# PCB-AC2.net
KiCad netlist of a schematic drawn in EAGLE
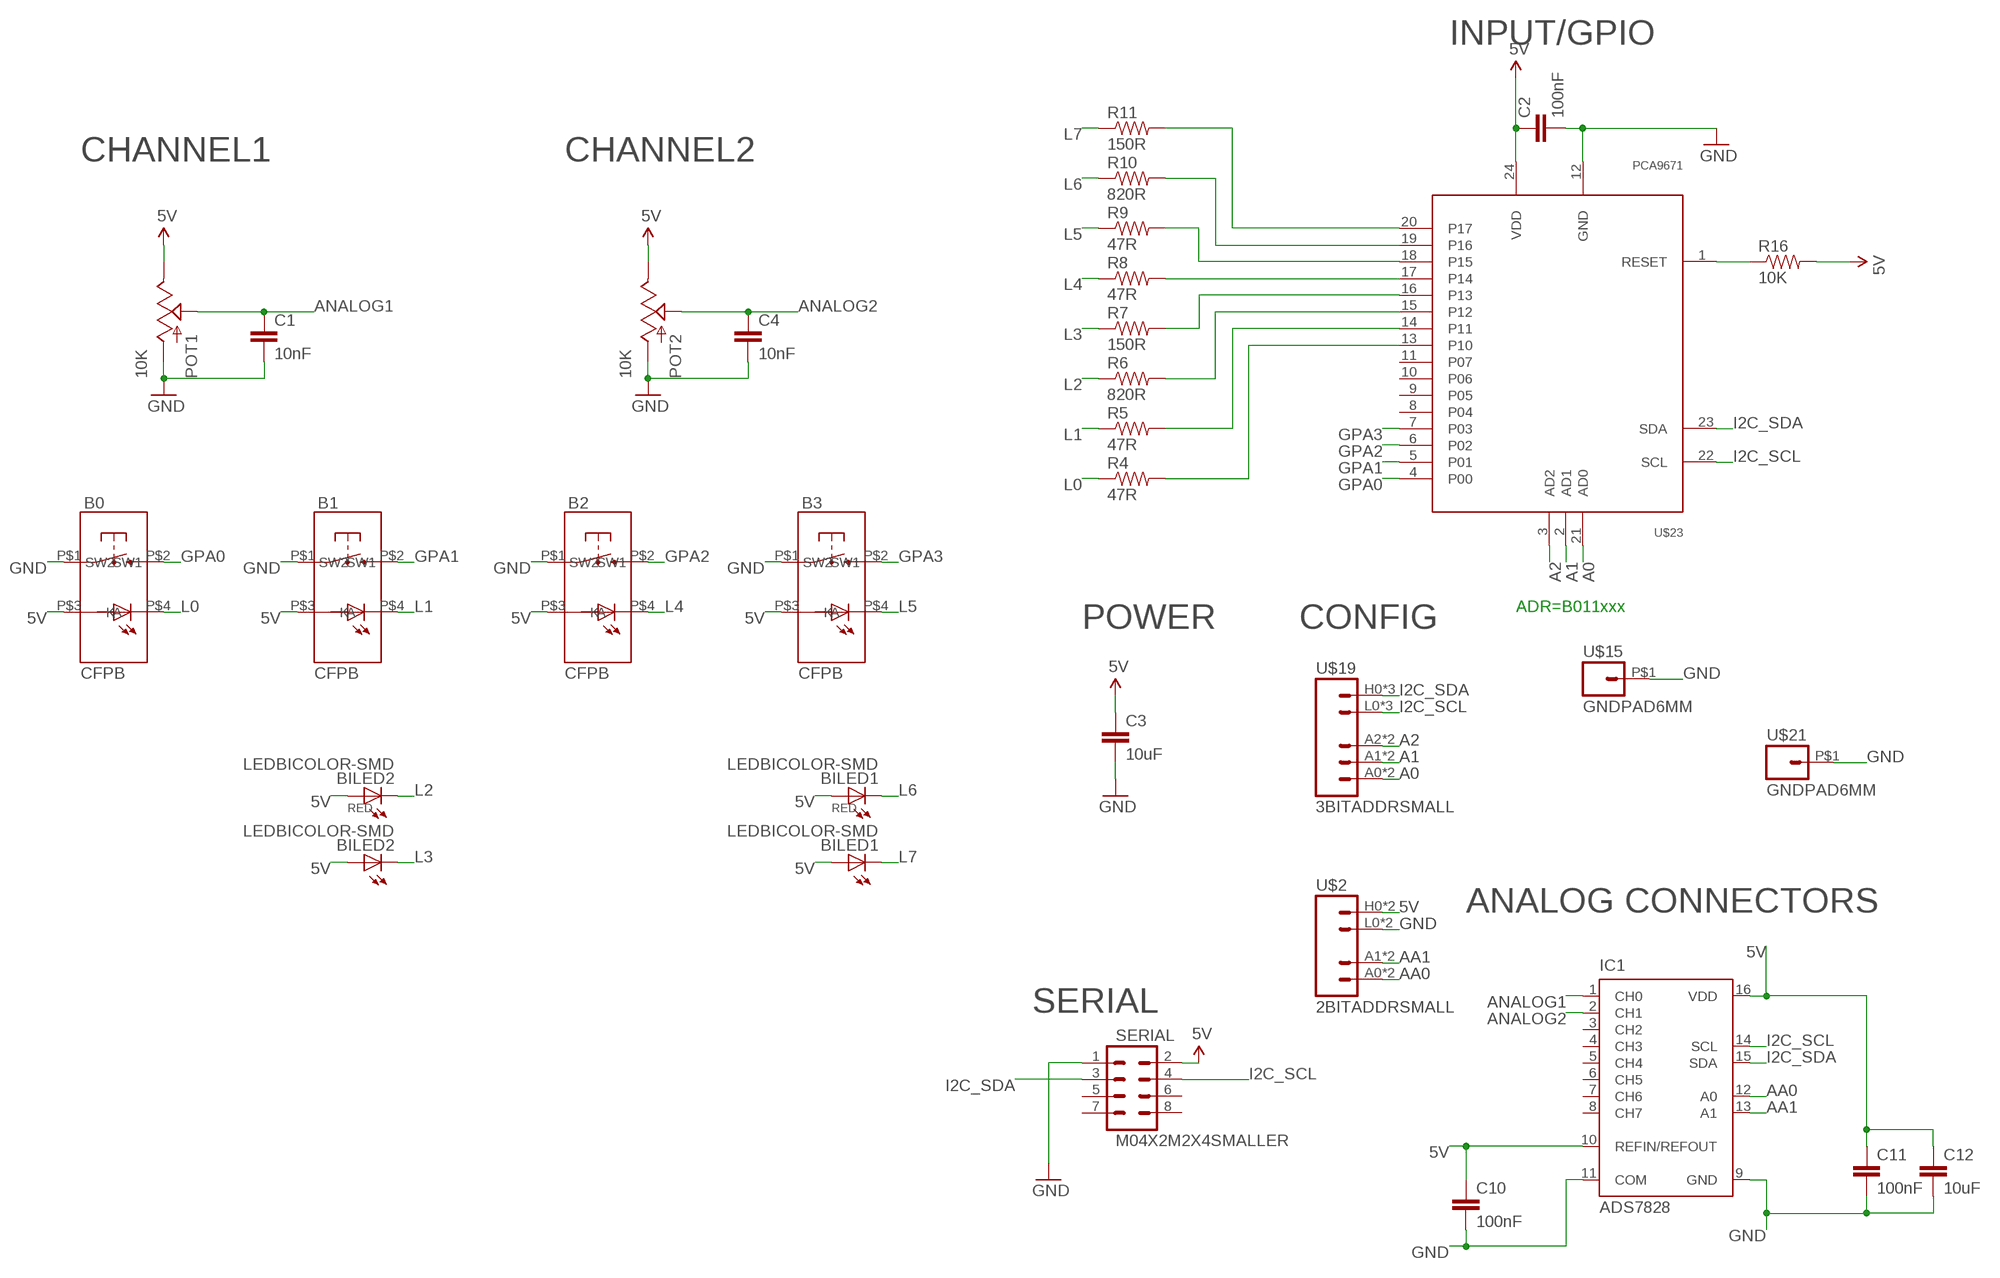
[diagram p0: schematic, sheet 1]

(export (version "E")
  (design (tool "Eeschema 10.0.6"))
  (components
    (comp (ref "B0")
      (value "CFPB")
      (footprint "eagle-import:CFPB-6_9MM")
      (libsource (lib "eagle-import") (part "CFPB"))
    )
    (comp (ref "B1")
      (value "CFPB")
      (footprint "eagle-import:CFPB-6_9MM")
      (libsource (lib "eagle-import") (part "CFPB"))
    )
    (comp (ref "B2")
      (value "CFPB")
      (footprint "eagle-import:CFPB-6_9MM")
      (libsource (lib "eagle-import") (part "CFPB"))
    )
    (comp (ref "B3")
      (value "CFPB")
      (footprint "eagle-import:CFPB-6_9MM")
      (libsource (lib "eagle-import") (part "CFPB"))
    )
    (comp (ref "BILED1")
      (value "LEDBICOLOR-SMD")
      (footprint "eagle-import:LEDBICOLOR-SMD")
      (libsource (lib "eagle-import") (part "LEDBICOLOR-SMD"))
    )
    (comp (ref "BILED2")
      (value "LEDBICOLOR-SMD")
      (footprint "eagle-import:LEDBICOLOR-SMD")
      (libsource (lib "eagle-import") (part "LEDBICOLOR-SMD"))
    )
    (comp (ref "C1")
      (value "10nF")
      (footprint "eagle-import:0603-CAP")
      (libsource (lib "eagle-import") (part "CAP0603-CAP"))
    )
    (comp (ref "C2")
      (value "100nF")
      (footprint "eagle-import:0603-CAP")
      (libsource (lib "eagle-import") (part "CAP0603-CAP"))
    )
    (comp (ref "C3")
      (value "10uF")
      (footprint "eagle-import:0805")
      (libsource (lib "eagle-import") (part "CAP0805"))
    )
    (comp (ref "C4")
      (value "10nF")
      (footprint "eagle-import:0603-CAP")
      (libsource (lib "eagle-import") (part "CAP0603-CAP"))
    )
    (comp (ref "C10")
      (value "100nF")
      (footprint "eagle-import:0603-CAP")
      (libsource (lib "eagle-import") (part "CAP0603-CAP"))
    )
    (comp (ref "C11")
      (value "100nF")
      (footprint "eagle-import:0603-CAP")
      (libsource (lib "eagle-import") (part "CAP0603-CAP"))
    )
    (comp (ref "C12")
      (value "10uF")
      (footprint "eagle-import:0805")
      (libsource (lib "eagle-import") (part "CAP0805"))
    )
    (comp (ref "IC1")
      (value "ADS7828")
      (footprint "eagle-import:TSSOP16-PW")
      (fields (field (name "MF") "TEXAS INSTRUMENTS") (field (name "MPN") "ADS7828E/250"))
      (libsource (lib "eagle-import") (part "ADS7828"))
    )
    (comp (ref "POT1")
      (value "10K")
      (footprint "eagle-import:ALPS_POT")
      (libsource (lib "eagle-import") (part "POT"))
    )
    (comp (ref "POT2")
      (value "10K")
      (footprint "eagle-import:ALPS_POT")
      (libsource (lib "eagle-import") (part "POT"))
    )
    (comp (ref "R4")
      (value "47R")
      (footprint "eagle-import:0603-RES")
      (libsource (lib "eagle-import") (part "RESISTOR0603-RES"))
    )
    (comp (ref "R5")
      (value "47R")
      (footprint "eagle-import:0603-RES")
      (libsource (lib "eagle-import") (part "RESISTOR0603-RES"))
    )
    (comp (ref "R6")
      (value "820R")
      (footprint "eagle-import:0603-RES")
      (libsource (lib "eagle-import") (part "RESISTOR0603-RES"))
    )
    (comp (ref "R7")
      (value "150R")
      (footprint "eagle-import:0603-RES")
      (libsource (lib "eagle-import") (part "RESISTOR0603-RES"))
    )
    (comp (ref "R8")
      (value "47R")
      (footprint "eagle-import:0603-RES")
      (libsource (lib "eagle-import") (part "RESISTOR0603-RES"))
    )
    (comp (ref "R9")
      (value "47R")
      (footprint "eagle-import:0603-RES")
      (libsource (lib "eagle-import") (part "RESISTOR0603-RES"))
    )
    (comp (ref "R10")
      (value "820R")
      (footprint "eagle-import:0603-RES")
      (libsource (lib "eagle-import") (part "RESISTOR0603-RES"))
    )
    (comp (ref "R11")
      (value "150R")
      (footprint "eagle-import:0603-RES")
      (libsource (lib "eagle-import") (part "RESISTOR0603-RES"))
    )
    (comp (ref "R16")
      (value "10K")
      (footprint "eagle-import:0603-RES")
      (libsource (lib "eagle-import") (part "RESISTOR0603-RES"))
    )
    (comp (ref "SERIAL")
      (value "M04X2M2X4SMALLER")
      (footprint "eagle-import:M2X4SMALLER")
      (libsource (lib "eagle-import") (part "M04X2M2X4SMALLER"))
    )
    (comp (ref "U$2")
      (value "2BITADDRSMALL")
      (footprint "eagle-import:2BITADDR_SMALL")
      (libsource (lib "eagle-import") (part "2BITADDRSMALL"))
    )
    (comp (ref "U$15")
      (value "GNDPAD6MM")
      (footprint "eagle-import:3.2MMPAD6MM")
      (libsource (lib "eagle-import") (part "GNDPAD6MM"))
    )
    (comp (ref "U$19")
      (value "3BITADDRSMALL")
      (footprint "eagle-import:3BITADDR_SMALL")
      (libsource (lib "eagle-import") (part "3BITADDRSMALL"))
    )
    (comp (ref "U$21")
      (value "GNDPAD6MM")
      (footprint "eagle-import:3.2MMPAD6MM")
      (libsource (lib "eagle-import") (part "GNDPAD6MM"))
    )
    (comp (ref "U$23")
      (value "PCA9671")
      (footprint "eagle-import:TSSOP24")
      (libsource (lib "eagle-import") (part "PCA9671"))
    )
  )
  (nets
    (net (code "1") (name "5V") (class "Default")
      (node (ref "B0") (pin "P$3") (pinfunction "A_P$3") (pintype "bidirectional"))
      (node (ref "B1") (pin "P$3") (pinfunction "A_P$3") (pintype "bidirectional"))
      (node (ref "B2") (pin "P$3") (pinfunction "A_P$3") (pintype "bidirectional"))
      (node (ref "B3") (pin "P$3") (pinfunction "A_P$3") (pintype "bidirectional"))
      (node (ref "BILED1") (pin "P$1") (pinfunction "A_P$1") (pintype "passive"))
      (node (ref "BILED1") (pin "P$3") (pinfunction "A1_P$3") (pintype "passive"))
      (node (ref "BILED2") (pin "P$1") (pinfunction "A_P$1") (pintype "passive"))
      (node (ref "BILED2") (pin "P$3") (pinfunction "A1_P$3") (pintype "passive"))
      (node (ref "C10") (pin "1") (pinfunction "1_1") (pintype "passive"))
      (node (ref "C11") (pin "1") (pinfunction "1_1") (pintype "passive"))
      (node (ref "C12") (pin "1") (pinfunction "1_1") (pintype "passive"))
      (node (ref "C2") (pin "1") (pinfunction "1_1") (pintype "passive"))
      (node (ref "C3") (pin "1") (pinfunction "1_1") (pintype "passive"))
      (node (ref "IC1") (pin "10") (pinfunction "REFIN/REFOUT_10") (pintype "passive"))
      (node (ref "IC1") (pin "16") (pinfunction "VDD_16") (pintype "power_in"))
      (node (ref "POT1") (pin "P$1") (pinfunction "E_P$1") (pintype "passive"))
      (node (ref "POT2") (pin "P$1") (pinfunction "E_P$1") (pintype "passive"))
      (node (ref "R16") (pin "2") (pinfunction "2_2") (pintype "passive"))
      (node (ref "SERIAL") (pin "2") (pinfunction "2_2") (pintype "passive"))
      (node (ref "U$2") (pin "H0") (pinfunction "VCC_H0") (pintype "passive"))
      (node (ref "U$2") (pin "H1") (pinfunction "VCC_H1") (pintype "passive"))
      (node (ref "U$23") (pin "24") (pinfunction "VDD_24") (pintype "power_in"))
    )
    (net (code "2") (name "A0") (class "Default")
      (node (ref "U$19") (pin "A0") (pinfunction "A0_A0") (pintype "passive"))
      (node (ref "U$19") (pin "AS0") (pinfunction "A0_AS0") (pintype "passive"))
      (node (ref "U$23") (pin "21") (pinfunction "AD0_21") (pintype "input"))
    )
    (net (code "3") (name "A1") (class "Default")
      (node (ref "U$19") (pin "A1") (pinfunction "A1_A1") (pintype "passive"))
      (node (ref "U$19") (pin "AS1") (pinfunction "A1_AS1") (pintype "passive"))
      (node (ref "U$23") (pin "2") (pinfunction "AD1_2") (pintype "input"))
    )
    (net (code "4") (name "A2") (class "Default")
      (node (ref "U$19") (pin "A2") (pinfunction "A2_A2") (pintype "passive"))
      (node (ref "U$19") (pin "AS2") (pinfunction "A2_AS2") (pintype "passive"))
      (node (ref "U$23") (pin "3") (pinfunction "AD2_3") (pintype "input"))
    )
    (net (code "5") (name "AA0") (class "Default")
      (node (ref "IC1") (pin "12") (pinfunction "A0_12") (pintype "input"))
      (node (ref "U$2") (pin "A0") (pinfunction "A1_A0") (pintype "passive"))
      (node (ref "U$2") (pin "AS0") (pinfunction "A1_AS0") (pintype "passive"))
    )
    (net (code "6") (name "AA1") (class "Default")
      (node (ref "IC1") (pin "13") (pinfunction "A1_13") (pintype "input"))
      (node (ref "U$2") (pin "A1") (pinfunction "A2_A1") (pintype "passive"))
      (node (ref "U$2") (pin "AS1") (pinfunction "A2_AS1") (pintype "passive"))
    )
    (net (code "7") (name "ANALOG1") (class "Default")
      (node (ref "C1") (pin "1") (pinfunction "1_1") (pintype "passive"))
      (node (ref "IC1") (pin "1") (pinfunction "CH0_1") (pintype "input"))
      (node (ref "POT1") (pin "P$2") (pinfunction "S_P$2") (pintype "passive"))
    )
    (net (code "8") (name "ANALOG2") (class "Default")
      (node (ref "C4") (pin "1") (pinfunction "1_1") (pintype "passive"))
      (node (ref "IC1") (pin "2") (pinfunction "CH1_2") (pintype "input"))
      (node (ref "POT2") (pin "P$2") (pinfunction "S_P$2") (pintype "passive"))
    )
    (net (code "9") (name "GND") (class "Default")
      (node (ref "B0") (pin "P$1") (pinfunction "SW1_P$1") (pintype "bidirectional"))
      (node (ref "B1") (pin "P$1") (pinfunction "SW1_P$1") (pintype "bidirectional"))
      (node (ref "B2") (pin "P$1") (pinfunction "SW1_P$1") (pintype "bidirectional"))
      (node (ref "B3") (pin "P$1") (pinfunction "SW1_P$1") (pintype "bidirectional"))
      (node (ref "C1") (pin "2") (pinfunction "2_2") (pintype "passive"))
      (node (ref "C10") (pin "2") (pinfunction "2_2") (pintype "passive"))
      (node (ref "C11") (pin "2") (pinfunction "2_2") (pintype "passive"))
      (node (ref "C12") (pin "2") (pinfunction "2_2") (pintype "passive"))
      (node (ref "C2") (pin "2") (pinfunction "2_2") (pintype "passive"))
      (node (ref "C3") (pin "2") (pinfunction "2_2") (pintype "passive"))
      (node (ref "C4") (pin "2") (pinfunction "2_2") (pintype "passive"))
      (node (ref "IC1") (pin "11") (pinfunction "COM_11") (pintype "input"))
      (node (ref "IC1") (pin "9") (pinfunction "GND_9") (pintype "power_in"))
      (node (ref "POT1") (pin "P$3") (pinfunction "A_P$3") (pintype "passive"))
      (node (ref "POT2") (pin "P$3") (pinfunction "A_P$3") (pintype "passive"))
      (node (ref "SERIAL") (pin "1") (pinfunction "1_1") (pintype "passive"))
      (node (ref "U$15") (pin "P$1") (pinfunction "1_P$1") (pintype "passive"))
      (node (ref "U$2") (pin "L0") (pinfunction "GND_L0") (pintype "passive"))
      (node (ref "U$2") (pin "L1") (pinfunction "GND_L1") (pintype "passive"))
      (node (ref "U$21") (pin "P$1") (pinfunction "1_P$1") (pintype "passive"))
      (node (ref "U$23") (pin "12") (pinfunction "GND_12") (pintype "power_in"))
    )
    (net (code "10") (name "GPA0") (class "Default")
      (node (ref "B0") (pin "P$2") (pinfunction "SW2_P$2") (pintype "bidirectional"))
      (node (ref "U$23") (pin "4") (pinfunction "P00_4") (pintype "output"))
    )
    (net (code "11") (name "GPA1") (class "Default")
      (node (ref "B1") (pin "P$2") (pinfunction "SW2_P$2") (pintype "bidirectional"))
      (node (ref "U$23") (pin "5") (pinfunction "P01_5") (pintype "output"))
    )
    (net (code "12") (name "GPA2") (class "Default")
      (node (ref "B2") (pin "P$2") (pinfunction "SW2_P$2") (pintype "bidirectional"))
      (node (ref "U$23") (pin "6") (pinfunction "P02_6") (pintype "output"))
    )
    (net (code "13") (name "GPA3") (class "Default")
      (node (ref "B3") (pin "P$2") (pinfunction "SW2_P$2") (pintype "bidirectional"))
      (node (ref "U$23") (pin "7") (pinfunction "P03_7") (pintype "output"))
    )
    (net (code "14") (name "I2C_SCL") (class "Default")
      (node (ref "IC1") (pin "14") (pinfunction "SCL_14") (pintype "input"))
      (node (ref "SERIAL") (pin "4") (pinfunction "4_4") (pintype "passive"))
      (node (ref "U$19") (pin "L0") (pinfunction "GND_L0") (pintype "passive"))
      (node (ref "U$19") (pin "L1") (pinfunction "GND_L1") (pintype "passive"))
      (node (ref "U$19") (pin "L2") (pinfunction "GND_L2") (pintype "passive"))
      (node (ref "U$23") (pin "22") (pinfunction "SCL_22") (pintype "input"))
    )
    (net (code "15") (name "I2C_SDA") (class "Default")
      (node (ref "IC1") (pin "15") (pinfunction "SDA_15") (pintype "bidirectional"))
      (node (ref "SERIAL") (pin "3") (pinfunction "3_3") (pintype "passive"))
      (node (ref "U$19") (pin "H0") (pinfunction "VCC_H0") (pintype "passive"))
      (node (ref "U$19") (pin "H1") (pinfunction "VCC_H1") (pintype "passive"))
      (node (ref "U$19") (pin "H2") (pinfunction "VCC_H2") (pintype "passive"))
      (node (ref "U$23") (pin "23") (pinfunction "SDA_23") (pintype "input"))
    )
    (net (code "16") (name "L0") (class "Default")
      (node (ref "B0") (pin "P$4") (pinfunction "K_P$4") (pintype "bidirectional"))
      (node (ref "R4") (pin "1") (pinfunction "1_1") (pintype "passive"))
    )
    (net (code "17") (name "L1") (class "Default")
      (node (ref "B1") (pin "P$4") (pinfunction "K_P$4") (pintype "bidirectional"))
      (node (ref "R5") (pin "1") (pinfunction "1_1") (pintype "passive"))
    )
    (net (code "18") (name "L2") (class "Default")
      (node (ref "BILED2") (pin "P$2") (pinfunction "C_P$2") (pintype "passive"))
      (node (ref "R6") (pin "1") (pinfunction "1_1") (pintype "passive"))
    )
    (net (code "19") (name "L3") (class "Default")
      (node (ref "BILED2") (pin "P$4") (pinfunction "C1_P$4") (pintype "passive"))
      (node (ref "R7") (pin "1") (pinfunction "1_1") (pintype "passive"))
    )
    (net (code "20") (name "L4") (class "Default")
      (node (ref "B2") (pin "P$4") (pinfunction "K_P$4") (pintype "bidirectional"))
      (node (ref "R8") (pin "1") (pinfunction "1_1") (pintype "passive"))
    )
    (net (code "21") (name "L5") (class "Default")
      (node (ref "B3") (pin "P$4") (pinfunction "K_P$4") (pintype "bidirectional"))
      (node (ref "R9") (pin "1") (pinfunction "1_1") (pintype "passive"))
    )
    (net (code "22") (name "L6") (class "Default")
      (node (ref "BILED1") (pin "P$2") (pinfunction "C_P$2") (pintype "passive"))
      (node (ref "R10") (pin "1") (pinfunction "1_1") (pintype "passive"))
    )
    (net (code "23") (name "L7") (class "Default")
      (node (ref "BILED1") (pin "P$4") (pinfunction "C1_P$4") (pintype "passive"))
      (node (ref "R11") (pin "1") (pinfunction "1_1") (pintype "passive"))
    )
    (net (code "24") (name "Net-(U$23-P10)") (class "Default")
      (node (ref "R4") (pin "2") (pinfunction "2_2") (pintype "passive"))
      (node (ref "U$23") (pin "13") (pinfunction "P10_13") (pintype "output"))
    )
    (net (code "25") (name "Net-(U$23-P11)") (class "Default")
      (node (ref "R5") (pin "2") (pinfunction "2_2") (pintype "passive"))
      (node (ref "U$23") (pin "14") (pinfunction "P11_14") (pintype "output"))
    )
    (net (code "26") (name "Net-(U$23-P12)") (class "Default")
      (node (ref "R6") (pin "2") (pinfunction "2_2") (pintype "passive"))
      (node (ref "U$23") (pin "15") (pinfunction "P12_15") (pintype "output"))
    )
    (net (code "27") (name "Net-(U$23-P13)") (class "Default")
      (node (ref "R7") (pin "2") (pinfunction "2_2") (pintype "passive"))
      (node (ref "U$23") (pin "16") (pinfunction "P13_16") (pintype "output"))
    )
    (net (code "28") (name "Net-(U$23-P14)") (class "Default")
      (node (ref "R8") (pin "2") (pinfunction "2_2") (pintype "passive"))
      (node (ref "U$23") (pin "17") (pinfunction "P14_17") (pintype "output"))
    )
    (net (code "29") (name "Net-(U$23-P15)") (class "Default")
      (node (ref "R9") (pin "2") (pinfunction "2_2") (pintype "passive"))
      (node (ref "U$23") (pin "18") (pinfunction "P15_18") (pintype "output"))
    )
    (net (code "30") (name "Net-(U$23-P16)") (class "Default")
      (node (ref "R10") (pin "2") (pinfunction "2_2") (pintype "passive"))
      (node (ref "U$23") (pin "19") (pinfunction "P16_19") (pintype "output"))
    )
    (net (code "31") (name "Net-(U$23-P17)") (class "Default")
      (node (ref "R11") (pin "2") (pinfunction "2_2") (pintype "passive"))
      (node (ref "U$23") (pin "20") (pinfunction "P17_20") (pintype "output"))
    )
    (net (code "32") (name "Net-(U$23-RESET)") (class "Default")
      (node (ref "R16") (pin "1") (pinfunction "1_1") (pintype "passive"))
      (node (ref "U$23") (pin "1") (pinfunction "RESET_1") (pintype "input"))
    )
    (net (code "33") (name "unconnected-(IC1-CH2-Pad3)") (class "Default")
      (node (ref "IC1") (pin "3") (pinfunction "CH2_3") (pintype "input"))
    )
    (net (code "34") (name "unconnected-(IC1-CH3-Pad4)") (class "Default")
      (node (ref "IC1") (pin "4") (pinfunction "CH3_4") (pintype "input"))
    )
    (net (code "35") (name "unconnected-(IC1-CH4-Pad5)") (class "Default")
      (node (ref "IC1") (pin "5") (pinfunction "CH4_5") (pintype "input"))
    )
    (net (code "36") (name "unconnected-(IC1-CH5-Pad6)") (class "Default")
      (node (ref "IC1") (pin "6") (pinfunction "CH5_6") (pintype "input"))
    )
    (net (code "37") (name "unconnected-(IC1-CH6-Pad7)") (class "Default")
      (node (ref "IC1") (pin "7") (pinfunction "CH6_7") (pintype "input"))
    )
    (net (code "38") (name "unconnected-(IC1-CH7-Pad8)") (class "Default")
      (node (ref "IC1") (pin "8") (pinfunction "CH7_8") (pintype "input"))
    )
    (net (code "39") (name "unconnected-(SERIAL-Pad5)") (class "Default")
      (node (ref "SERIAL") (pin "5") (pinfunction "5_5") (pintype "passive"))
    )
    (net (code "40") (name "unconnected-(SERIAL-Pad6)") (class "Default")
      (node (ref "SERIAL") (pin "6") (pinfunction "6_6") (pintype "passive"))
    )
    (net (code "41") (name "unconnected-(SERIAL-Pad7)") (class "Default")
      (node (ref "SERIAL") (pin "7") (pinfunction "7_7") (pintype "passive"))
    )
    (net (code "42") (name "unconnected-(SERIAL-Pad8)") (class "Default")
      (node (ref "SERIAL") (pin "8") (pinfunction "8_8") (pintype "passive"))
    )
    (net (code "43") (name "unconnected-(U$23-P04-Pad8)") (class "Default")
      (node (ref "U$23") (pin "8") (pinfunction "P04_8") (pintype "output"))
    )
    (net (code "44") (name "unconnected-(U$23-P05-Pad9)") (class "Default")
      (node (ref "U$23") (pin "9") (pinfunction "P05_9") (pintype "output"))
    )
    (net (code "45") (name "unconnected-(U$23-P06-Pad10)") (class "Default")
      (node (ref "U$23") (pin "10") (pinfunction "P06_10") (pintype "output"))
    )
    (net (code "46") (name "unconnected-(U$23-P07-Pad11)") (class "Default")
      (node (ref "U$23") (pin "11") (pinfunction "P07_11") (pintype "output"))
    )
  )
)
